# robot_arm_board.net
KiCad netlist of a schematic drawn in EasyEDA Pro
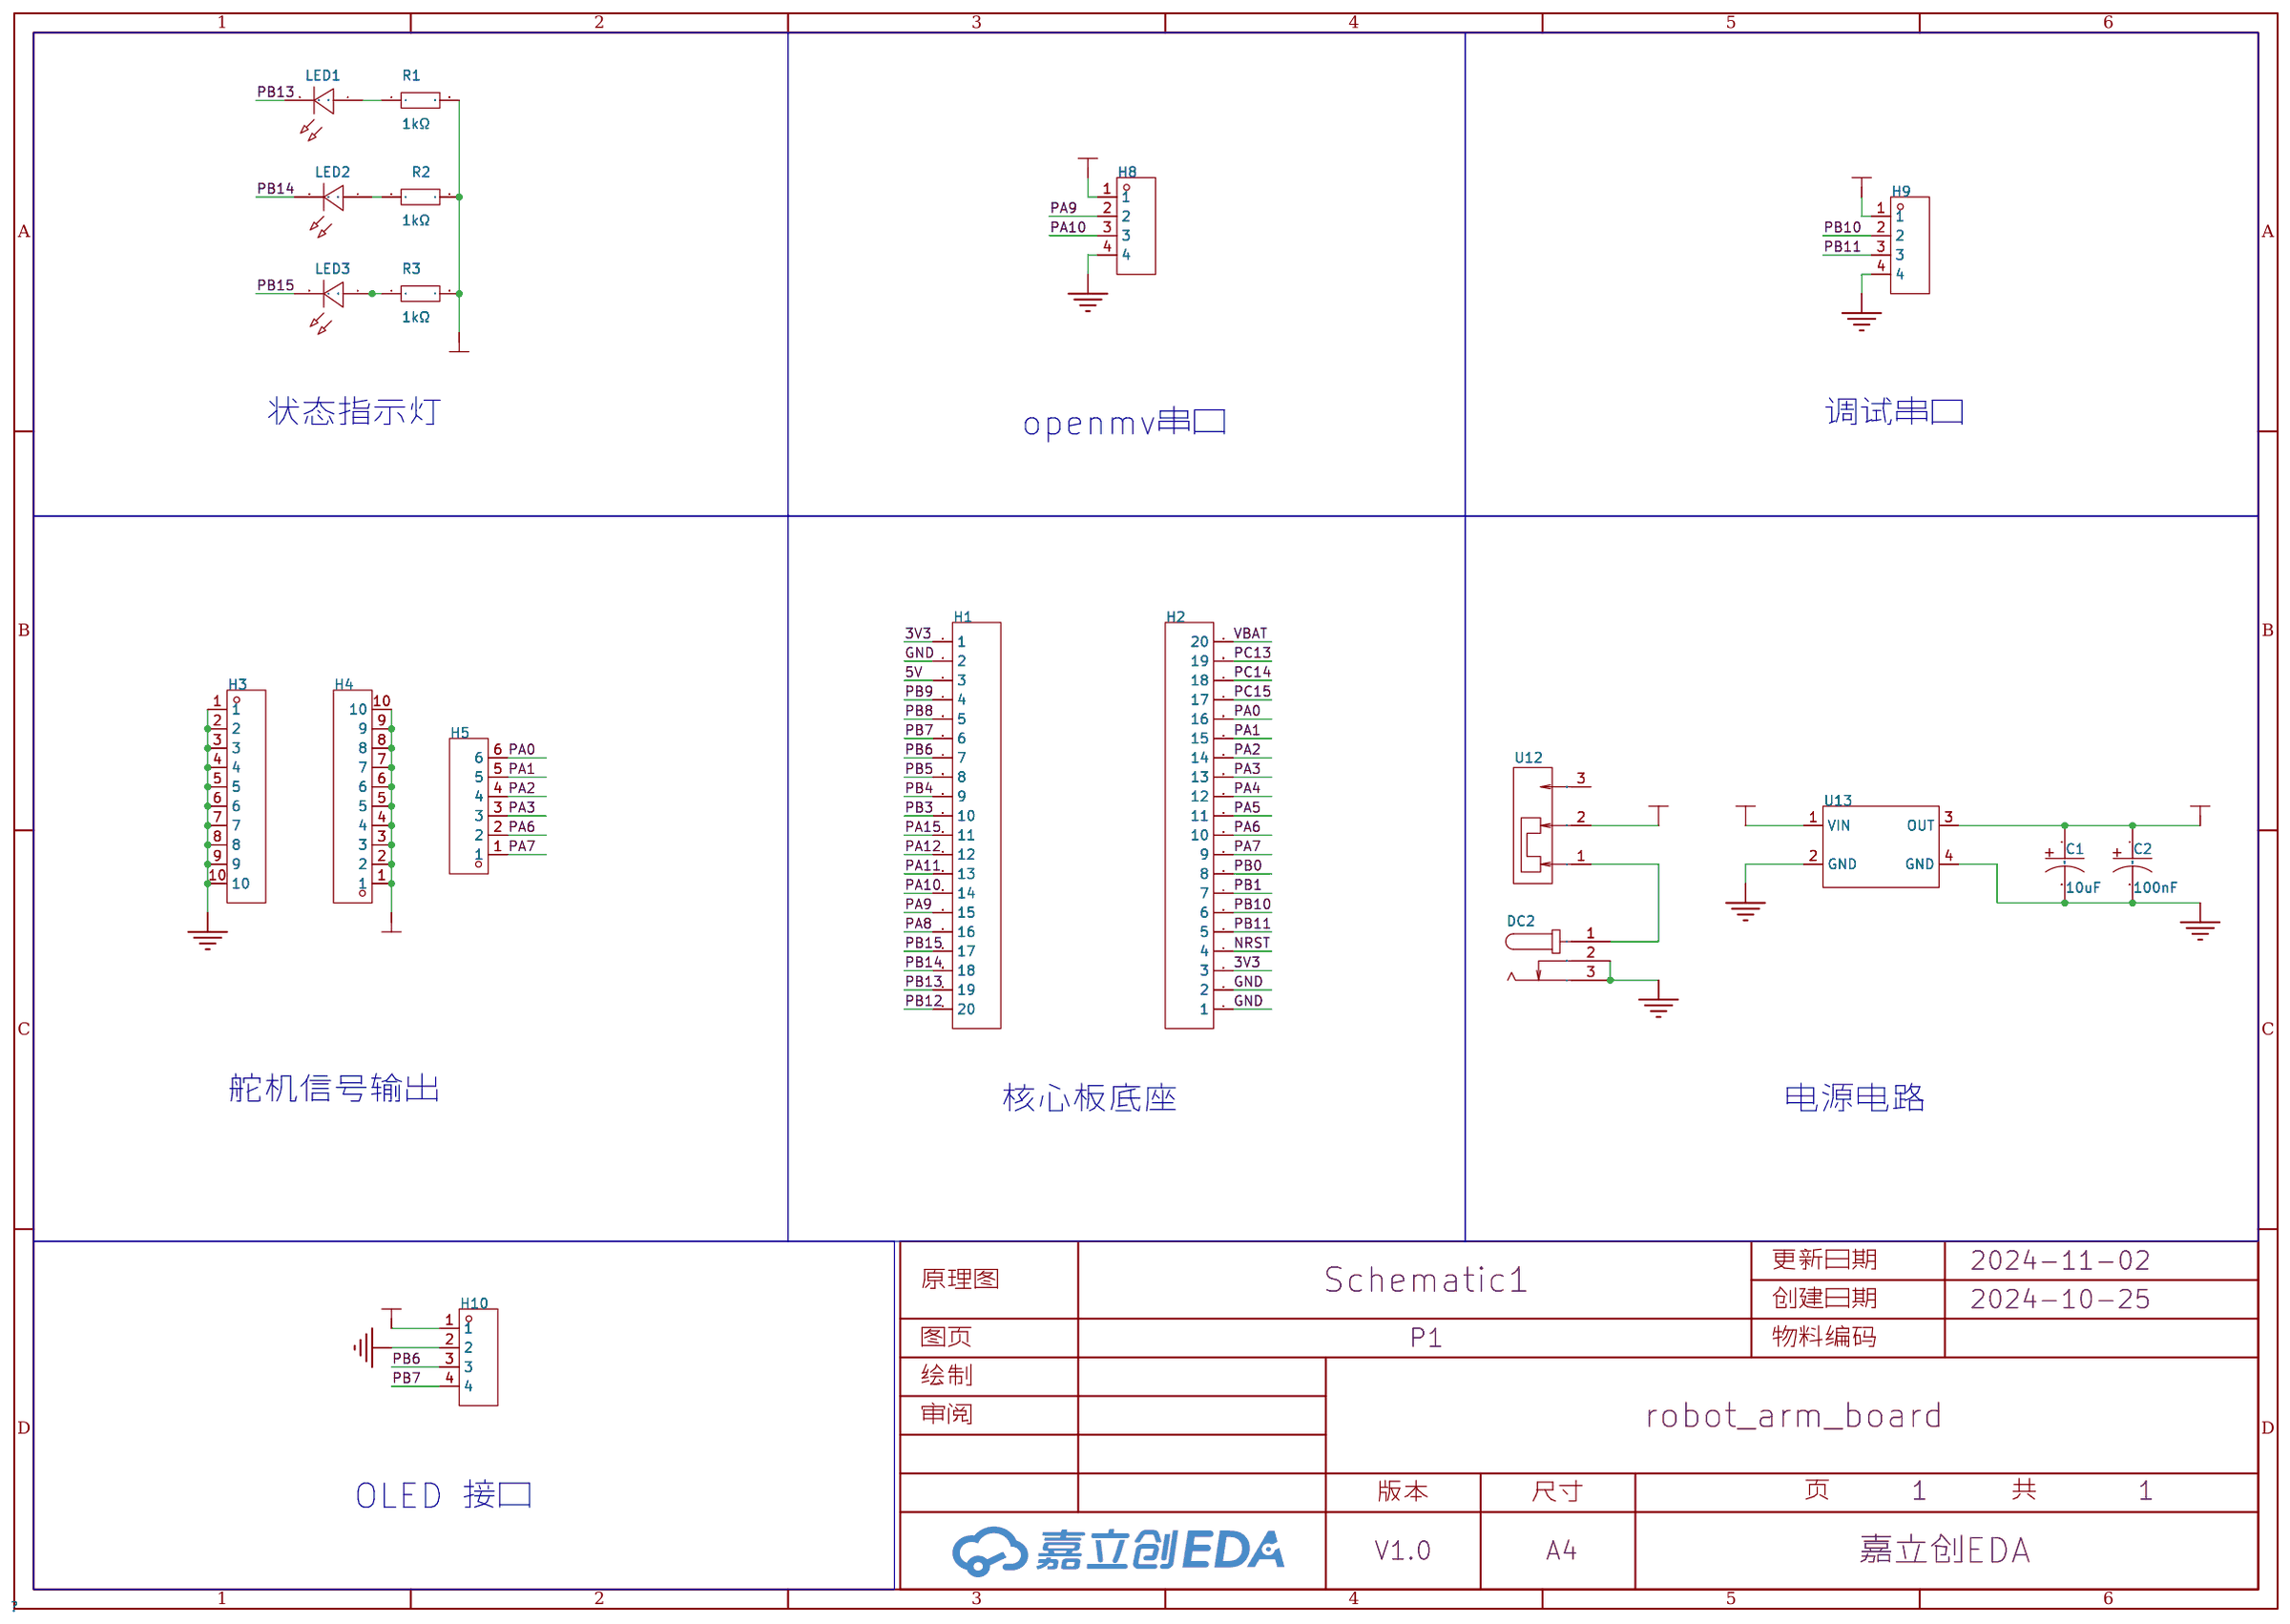
[diagram p0: schematic sheet]

(export (version "E")
  (design (tool "Eeschema 10.0.6"))
  (components
    (comp (ref "C1")
      (value "10uF")
      (footprint "easyedapro:CAP-TH_BD6.3-P2.50-D0.5-FD")
      (libsource (lib "easyedapro") (part "CAP,铝电解电容,470UF,7*12"))
    )
    (comp (ref "C2")
      (value "100nF")
      (footprint "easyedapro:CAP-TH_BD6.3-P2.50-D0.5-FD")
      (libsource (lib "easyedapro") (part "CAP,铝电解电容,470UF,7*12"))
    )
    (comp (ref "DC2")
      (value "~")
      (description "连接器类型:DC电源插座;安装方式:弯插;触点内径:-;触点外径:6.4mm;额定电流:1A;额定电压:30V;工作温度范围:-25~+70;")
      (fields
        (field (name "Manufacturer Part") "KH-DC-005-2.5")
        (field (name "Manufacturer") "kinghelm(金航标)")
      )
      (libsource (lib "easyedapro") (part "KH-DC-005-2.5"))
    )
    (comp (ref "H1")
      (value "~")
      (footprint "easyedapro:HDR-TH_20P-P2.54-V-F")
      (libsource (lib "easyedapro") (part "HDR-F_2.54_1x20P"))
    )
    (comp (ref "H2")
      (value "~")
      (footprint "easyedapro:HDR-TH_20P-P2.54-V-F")
      (libsource (lib "easyedapro") (part "HDR-F_2.54_1x20P"))
    )
    (comp (ref "H3")
      (value "~")
      (footprint "easyedapro:HDR-TH_10P-P2.54-V-F")
      (libsource (lib "easyedapro") (part "X5511FV-10-C70D30-1000"))
    )
    (comp (ref "H4")
      (value "~")
      (footprint "easyedapro:HDR-TH_10P-P2.54-V-F")
      (libsource (lib "easyedapro") (part "X5511FV-10-C70D30-1000"))
    )
    (comp (ref "H5")
      (value "~")
      (footprint "easyedapro:hdr-th_6p-p2.54-v-f")
      (libsource (lib "easyedapro") (part "Header-Female-2.54_1x6"))
    )
    (comp (ref "H8")
      (value "~")
      (footprint "easyedapro:hdr-th_4p-p2.54-v-f")
      (libsource (lib "easyedapro") (part "2.54-1*4P母"))
    )
    (comp (ref "H9")
      (value "~")
      (footprint "easyedapro:hdr-th_4p-p2.54-v-f")
      (libsource (lib "easyedapro") (part "2.54-1*4P母"))
    )
    (comp (ref "H10")
      (value "~")
      (footprint "easyedapro:hdr-th_4p-p2.54-v-f")
      (libsource (lib "easyedapro") (part "2.54-1*4P母"))
    )
    (comp (ref "LED1")
      (value "~")
      (footprint "easyedapro:LED_TH-3mm")
      (libsource (lib "easyedapro") (part "LED_TH-G"))
    )
    (comp (ref "LED2")
      (value "~")
      (footprint "easyedapro:LED_TH-3mm")
      (libsource (lib "easyedapro") (part "LED_TH-G"))
    )
    (comp (ref "LED3")
      (value "~")
      (footprint "easyedapro:LED_TH-3mm")
      (libsource (lib "easyedapro") (part "LED_TH-G"))
    )
    (comp (ref "R1")
      (value "1kΩ")
      (footprint "easyedapro:Res_1/8W")
      (libsource (lib "easyedapro") (part "电阻"))
    )
    (comp (ref "R2")
      (value "1kΩ")
      (footprint "easyedapro:Res_1/8W")
      (libsource (lib "easyedapro") (part "电阻"))
    )
    (comp (ref "R3")
      (value "1kΩ")
      (footprint "easyedapro:Res_1/8W")
      (libsource (lib "easyedapro") (part "电阻"))
    )
    (comp (ref "U12")
      (value "SS-12D10-G5")
      (footprint "easyedapro:SW-TH_SS-12D10-G050")
      (description "电路结构:单刀双掷;安装方式:直插;开关颜色:黑色;滑钮形状:矩形柱状;引脚样式:PC引脚;开关长度:12.7mm;开关宽度:6.7mm;开关高度:11.3mm;")
      (fields (field (name "Manufacturer") "DEALON(德艺隆)"))
      (libsource (lib "easyedapro") (part "SS-12D10-G5"))
    )
    (comp (ref "U13")
      (value "~")
      (footprint "easyedapro:MP1584模块")
      (libsource (lib "easyedapro") (part "MP1584模块"))
    )
  )
  (nets
    (net (code "1") (name "+12V") (class "Default")
      (node (ref "U12") (pin "2") (pinfunction "2_2") (pintype "input"))
      (node (ref "U13") (pin "1") (pinfunction "VIN_1") (pintype "unspecified"))
    )
    (net (code "2") (name "/NRST") (class "Default")
      (node (ref "H2") (pin "4") (pinfunction "4_4") (pintype "input"))
    )
    (net (code "3") (name "/PA0") (class "Default")
      (node (ref "H2") (pin "16") (pinfunction "16_16") (pintype "input"))
      (node (ref "H5") (pin "6") (pinfunction "6_6") (pintype "unspecified"))
    )
    (net (code "4") (name "/PA1") (class "Default")
      (node (ref "H2") (pin "15") (pinfunction "15_15") (pintype "input"))
      (node (ref "H5") (pin "5") (pinfunction "5_5") (pintype "unspecified"))
    )
    (net (code "5") (name "/PA2") (class "Default")
      (node (ref "H2") (pin "14") (pinfunction "14_14") (pintype "input"))
      (node (ref "H5") (pin "4") (pinfunction "4_4") (pintype "unspecified"))
    )
    (net (code "6") (name "/PA3") (class "Default")
      (node (ref "H2") (pin "13") (pinfunction "13_13") (pintype "input"))
      (node (ref "H5") (pin "3") (pinfunction "3_3") (pintype "unspecified"))
    )
    (net (code "7") (name "/PA4") (class "Default")
      (node (ref "H2") (pin "12") (pinfunction "12_12") (pintype "input"))
    )
    (net (code "8") (name "/PA5") (class "Default")
      (node (ref "H2") (pin "11") (pinfunction "11_11") (pintype "input"))
    )
    (net (code "9") (name "/PA6") (class "Default")
      (node (ref "H2") (pin "10") (pinfunction "10_10") (pintype "input"))
      (node (ref "H5") (pin "2") (pinfunction "2_2") (pintype "unspecified"))
    )
    (net (code "10") (name "/PA7") (class "Default")
      (node (ref "H2") (pin "9") (pinfunction "9_9") (pintype "input"))
      (node (ref "H5") (pin "1") (pinfunction "1_1") (pintype "unspecified"))
    )
    (net (code "11") (name "/PA8") (class "Default")
      (node (ref "H1") (pin "16") (pinfunction "16_16") (pintype "input"))
    )
    (net (code "12") (name "/PA9") (class "Default")
      (node (ref "H1") (pin "15") (pinfunction "15_15") (pintype "input"))
      (node (ref "H8") (pin "2") (pinfunction "2_2") (pintype "unspecified"))
    )
    (net (code "13") (name "/PA10") (class "Default")
      (node (ref "H1") (pin "14") (pinfunction "14_14") (pintype "input"))
      (node (ref "H8") (pin "3") (pinfunction "3_3") (pintype "unspecified"))
    )
    (net (code "14") (name "/PA11") (class "Default")
      (node (ref "H1") (pin "13") (pinfunction "13_13") (pintype "input"))
    )
    (net (code "15") (name "/PA12") (class "Default")
      (node (ref "H1") (pin "12") (pinfunction "12_12") (pintype "input"))
    )
    (net (code "16") (name "/PA15") (class "Default")
      (node (ref "H1") (pin "11") (pinfunction "11_11") (pintype "input"))
    )
    (net (code "17") (name "/PB0") (class "Default")
      (node (ref "H2") (pin "8") (pinfunction "8_8") (pintype "input"))
    )
    (net (code "18") (name "/PB1") (class "Default")
      (node (ref "H2") (pin "7") (pinfunction "7_7") (pintype "input"))
    )
    (net (code "19") (name "/PB3") (class "Default")
      (node (ref "H1") (pin "10") (pinfunction "10_10") (pintype "input"))
    )
    (net (code "20") (name "/PB4") (class "Default")
      (node (ref "H1") (pin "9") (pinfunction "9_9") (pintype "input"))
    )
    (net (code "21") (name "/PB5") (class "Default")
      (node (ref "H1") (pin "8") (pinfunction "8_8") (pintype "input"))
    )
    (net (code "22") (name "/PB6") (class "Default")
      (node (ref "H1") (pin "7") (pinfunction "7_7") (pintype "input"))
      (node (ref "H10") (pin "3") (pinfunction "3_3") (pintype "unspecified"))
    )
    (net (code "23") (name "/PB7") (class "Default")
      (node (ref "H1") (pin "6") (pinfunction "6_6") (pintype "input"))
      (node (ref "H10") (pin "4") (pinfunction "4_4") (pintype "unspecified"))
    )
    (net (code "24") (name "/PB8") (class "Default")
      (node (ref "H1") (pin "5") (pinfunction "5_5") (pintype "input"))
    )
    (net (code "25") (name "/PB9") (class "Default")
      (node (ref "H1") (pin "4") (pinfunction "4_4") (pintype "input"))
    )
    (net (code "26") (name "/PB10") (class "Default")
      (node (ref "H2") (pin "6") (pinfunction "6_6") (pintype "input"))
      (node (ref "H9") (pin "2") (pinfunction "2_2") (pintype "unspecified"))
    )
    (net (code "27") (name "/PB11") (class "Default")
      (node (ref "H2") (pin "5") (pinfunction "5_5") (pintype "input"))
      (node (ref "H9") (pin "3") (pinfunction "3_3") (pintype "unspecified"))
    )
    (net (code "28") (name "/PB12") (class "Default")
      (node (ref "H1") (pin "20") (pinfunction "20_20") (pintype "input"))
    )
    (net (code "29") (name "/PB13") (class "Default")
      (node (ref "H1") (pin "19") (pinfunction "19_19") (pintype "input"))
      (node (ref "LED1") (pin "2") (pinfunction "A_2") (pintype "input"))
    )
    (net (code "30") (name "/PB14") (class "Default")
      (node (ref "H1") (pin "18") (pinfunction "18_18") (pintype "input"))
      (node (ref "LED2") (pin "2") (pinfunction "A_2") (pintype "input"))
    )
    (net (code "31") (name "/PB15") (class "Default")
      (node (ref "H1") (pin "17") (pinfunction "17_17") (pintype "input"))
      (node (ref "LED3") (pin "2") (pinfunction "A_2") (pintype "input"))
    )
    (net (code "32") (name "/PC13") (class "Default")
      (node (ref "H2") (pin "19") (pinfunction "19_19") (pintype "input"))
    )
    (net (code "33") (name "/PC14") (class "Default")
      (node (ref "H2") (pin "18") (pinfunction "18_18") (pintype "input"))
    )
    (net (code "34") (name "/PC15") (class "Default")
      (node (ref "H2") (pin "17") (pinfunction "17_17") (pintype "input"))
    )
    (net (code "35") (name "/VBAT") (class "Default")
      (node (ref "H2") (pin "20") (pinfunction "20_20") (pintype "input"))
    )
    (net (code "36") (name "3V3") (class "Default")
      (node (ref "H1") (pin "1") (pinfunction "1_1") (pintype "input"))
      (node (ref "H10") (pin "1") (pinfunction "1_1") (pintype "unspecified"))
      (node (ref "H2") (pin "3") (pinfunction "3_3") (pintype "input"))
      (node (ref "H8") (pin "1") (pinfunction "1_1") (pintype "unspecified"))
      (node (ref "H9") (pin "1") (pinfunction "1_1") (pintype "unspecified"))
      (node (ref "R1") (pin "2") (pinfunction "2_2") (pintype "input"))
      (node (ref "R2") (pin "2") (pinfunction "2_2") (pintype "input"))
      (node (ref "R3") (pin "2") (pinfunction "2_2") (pintype "input"))
    )
    (net (code "37") (name "5V") (class "Default")
      (node (ref "C1") (pin "1") (pinfunction "1_1") (pintype "unspecified"))
      (node (ref "C2") (pin "1") (pinfunction "1_1") (pintype "unspecified"))
      (node (ref "H1") (pin "3") (pinfunction "3_3") (pintype "input"))
      (node (ref "H4") (pin "1") (pinfunction "1_1") (pintype "unspecified"))
      (node (ref "H4") (pin "10") (pinfunction "10_10") (pintype "unspecified"))
      (node (ref "H4") (pin "2") (pinfunction "2_2") (pintype "unspecified"))
      (node (ref "H4") (pin "3") (pinfunction "3_3") (pintype "unspecified"))
      (node (ref "H4") (pin "4") (pinfunction "4_4") (pintype "unspecified"))
      (node (ref "H4") (pin "5") (pinfunction "5_5") (pintype "unspecified"))
      (node (ref "H4") (pin "6") (pinfunction "6_6") (pintype "unspecified"))
      (node (ref "H4") (pin "7") (pinfunction "7_7") (pintype "unspecified"))
      (node (ref "H4") (pin "8") (pinfunction "8_8") (pintype "unspecified"))
      (node (ref "H4") (pin "9") (pinfunction "9_9") (pintype "unspecified"))
      (node (ref "U13") (pin "3") (pinfunction "OUT_3") (pintype "unspecified"))
    )
    (net (code "38") (name "GND") (class "Default")
      (node (ref "C1") (pin "2") (pinfunction "2_2") (pintype "unspecified"))
      (node (ref "C2") (pin "2") (pinfunction "2_2") (pintype "unspecified"))
      (node (ref "DC2") (pin "2") (pinfunction "2_2") (pintype "input"))
      (node (ref "DC2") (pin "3") (pinfunction "3_3") (pintype "input"))
      (node (ref "H1") (pin "2") (pinfunction "2_2") (pintype "input"))
      (node (ref "H10") (pin "2") (pinfunction "2_2") (pintype "unspecified"))
      (node (ref "H2") (pin "1") (pinfunction "1_1") (pintype "input"))
      (node (ref "H2") (pin "2") (pinfunction "2_2") (pintype "input"))
      (node (ref "H3") (pin "1") (pinfunction "1_1") (pintype "unspecified"))
      (node (ref "H3") (pin "10") (pinfunction "10_10") (pintype "unspecified"))
      (node (ref "H3") (pin "2") (pinfunction "2_2") (pintype "unspecified"))
      (node (ref "H3") (pin "3") (pinfunction "3_3") (pintype "unspecified"))
      (node (ref "H3") (pin "4") (pinfunction "4_4") (pintype "unspecified"))
      (node (ref "H3") (pin "5") (pinfunction "5_5") (pintype "unspecified"))
      (node (ref "H3") (pin "6") (pinfunction "6_6") (pintype "unspecified"))
      (node (ref "H3") (pin "7") (pinfunction "7_7") (pintype "unspecified"))
      (node (ref "H3") (pin "8") (pinfunction "8_8") (pintype "unspecified"))
      (node (ref "H3") (pin "9") (pinfunction "9_9") (pintype "unspecified"))
      (node (ref "H8") (pin "4") (pinfunction "4_4") (pintype "unspecified"))
      (node (ref "H9") (pin "4") (pinfunction "4_4") (pintype "unspecified"))
      (node (ref "U13") (pin "2") (pinfunction "GND_2") (pintype "unspecified"))
      (node (ref "U13") (pin "4") (pinfunction "GND_4") (pintype "unspecified"))
    )
    (net (code "39") (name "Net-(DC2-Pad1)") (class "Default")
      (node (ref "DC2") (pin "1") (pinfunction "1_1") (pintype "input"))
      (node (ref "U12") (pin "1") (pinfunction "1_1") (pintype "input"))
    )
    (net (code "40") (name "Net-(LED1-C)") (class "Default")
      (node (ref "LED1") (pin "1") (pinfunction "C_1") (pintype "input"))
      (node (ref "R1") (pin "1") (pinfunction "1_1") (pintype "input"))
    )
    (net (code "41") (name "Net-(LED2-C)") (class "Default")
      (node (ref "LED2") (pin "1") (pinfunction "C_1") (pintype "input"))
      (node (ref "R2") (pin "1") (pinfunction "1_1") (pintype "input"))
    )
    (net (code "42") (name "Net-(LED3-C)") (class "Default")
      (node (ref "LED3") (pin "1") (pinfunction "C_1") (pintype "input"))
      (node (ref "R3") (pin "1") (pinfunction "1_1") (pintype "input"))
    )
    (net (code "43") (name "unconnected-(U12-Pad3)") (class "Default")
      (node (ref "U12") (pin "3") (pinfunction "3_3") (pintype "input"))
    )
  )
)
